# esp-module-ou.net
KiCad netlist of a schematic drawn in EAGLE
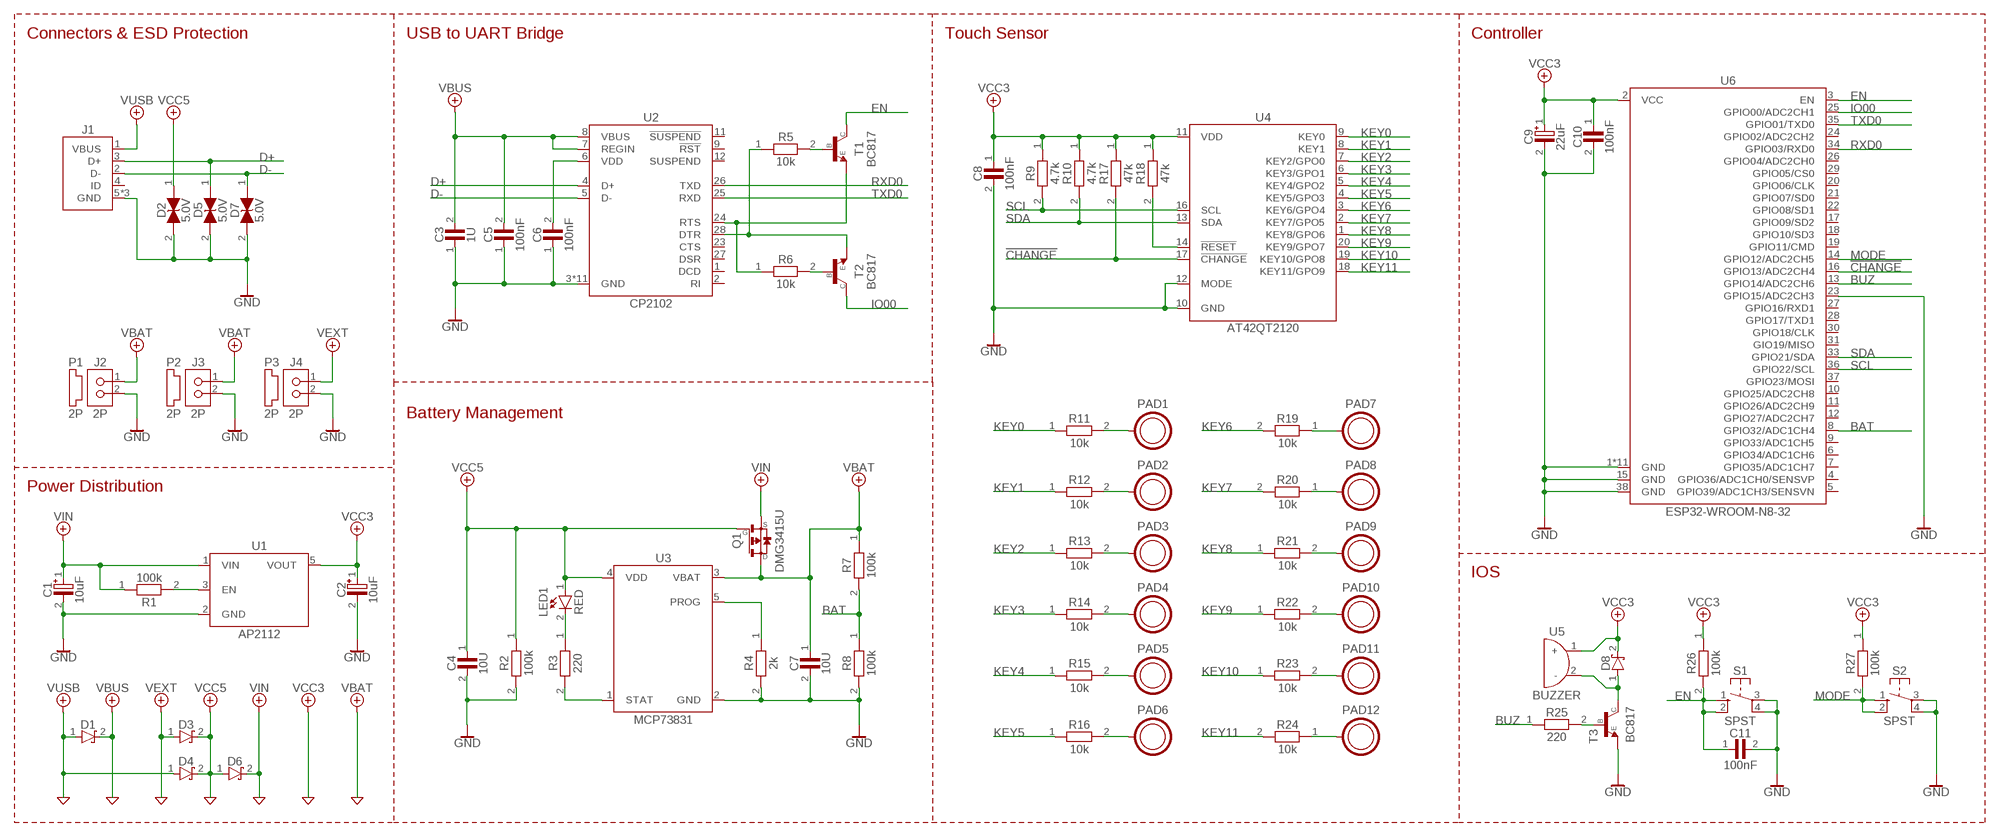
[diagram p0: schematic, sheet 1]

(export (version "E")
  (design (tool "Eeschema 10.0.6"))
  (components
    (comp (ref "C1")
      (value "10uF")
      (footprint "eagle-import:I1206-M3216-D")
      (fields
        (field (name "MF") "Kyocera AVX")
        (field (name "MPN") "TAJA106K016RNJ")
        (field (name "VOLTAGE") "16V")
      )
      (libsource (lib "eagle-import") (part "CAPACITOR-TANTALUM-I1206-M3216-10U"))
    )
    (comp (ref "C2")
      (value "10uF")
      (footprint "eagle-import:I1206-M3216-D")
      (fields
        (field (name "MF") "Kyocera AVX")
        (field (name "MPN") "TAJA106K016RNJ")
        (field (name "VOLTAGE") "16V")
      )
      (libsource (lib "eagle-import") (part "CAPACITOR-TANTALUM-I1206-M3216-10U"))
    )
    (comp (ref "C3")
      (value "1U")
      (footprint "eagle-import:I0805-M2012-C")
      (fields
        (field (name "MF") " FH (Guangdong Fenghua Advanced Tech)")
        (field (name "MPN") "0805B105K500NT")
        (field (name "TOLERANCE") "10%")
      )
      (libsource (lib "eagle-import") (part "CAPACITOR-CERAMIC-I0805-M2012-1U"))
    )
    (comp (ref "C4")
      (value "10U")
      (footprint "eagle-import:I0805-M2012-C")
      (fields
        (field (name "MF") "Samsung Electro-Mechanics")
        (field (name "MPN") "CL21A106KAYNNNE")
        (field (name "TOLERANCE") "10%")
      )
      (libsource (lib "eagle-import") (part "CAPACITOR-CERAMIC-I0805-M2012-10U"))
    )
    (comp (ref "C5")
      (value "100nF")
      (footprint "eagle-import:I0805-M2012-C")
      (fields
        (field (name "MF") "FH (Guangdong Fenghua Advanced Tech)")
        (field (name "MPN") "0805B104K500NT")
        (field (name "TOLERANCE") "10%")
      )
      (libsource (lib "eagle-import") (part "CAPACITOR-CERAMIC-I0805-M2012-100N"))
    )
    (comp (ref "C6")
      (value "100nF")
      (footprint "eagle-import:I0805-M2012-C")
      (fields
        (field (name "MF") "FH (Guangdong Fenghua Advanced Tech)")
        (field (name "MPN") "0805B104K500NT")
        (field (name "TOLERANCE") "10%")
      )
      (libsource (lib "eagle-import") (part "CAPACITOR-CERAMIC-I0805-M2012-100N"))
    )
    (comp (ref "C7")
      (value "10U")
      (footprint "eagle-import:I0805-M2012-C")
      (fields
        (field (name "MF") "Samsung Electro-Mechanics")
        (field (name "MPN") "CL21A106KAYNNNE")
        (field (name "TOLERANCE") "10%")
      )
      (libsource (lib "eagle-import") (part "CAPACITOR-CERAMIC-I0805-M2012-10U"))
    )
    (comp (ref "C8")
      (value "100nF")
      (footprint "eagle-import:I0805-M2012-C")
      (fields
        (field (name "MF") "FH (Guangdong Fenghua Advanced Tech)")
        (field (name "MPN") "0805B104K500NT")
        (field (name "TOLERANCE") "10%")
      )
      (libsource (lib "eagle-import") (part "CAPACITOR-CERAMIC-I0805-M2012-100N"))
    )
    (comp (ref "C9")
      (value "22uF")
      (footprint "eagle-import:I1206-M3216-D")
      (fields
        (field (name "MF") "Kyocera AVX")
        (field (name "MPN") "TAJA226K010RNJ")
        (field (name "VOLTAGE") "10V")
      )
      (libsource (lib "eagle-import") (part "CAPACITOR-TANTALUM-I1206-M3216-22U"))
    )
    (comp (ref "C10")
      (value "100nF")
      (footprint "eagle-import:I0805-M2012-C")
      (fields
        (field (name "MF") "FH (Guangdong Fenghua Advanced Tech)")
        (field (name "MPN") "0805B104K500NT")
        (field (name "TOLERANCE") "10%")
      )
      (libsource (lib "eagle-import") (part "CAPACITOR-CERAMIC-I0805-M2012-100N"))
    )
    (comp (ref "C11")
      (value "100nF")
      (footprint "eagle-import:I0805-M2012-C")
      (fields
        (field (name "MF") "FH (Guangdong Fenghua Advanced Tech)")
        (field (name "MPN") "0805B104K500NT")
        (field (name "TOLERANCE") "10%")
      )
      (libsource (lib "eagle-import") (part "CAPACITOR-CERAMIC-I0805-M2012-100N"))
    )
    (comp (ref "D1")
      (value "30V")
      (footprint "eagle-import:SOD-323")
      (fields (field (name "MF") "Diodes Incorporated") (field (name "MPN") "BAT760-7"))
      (libsource (lib "eagle-import") (part "SCHOTTKY-SOD-323-30V"))
    )
    (comp (ref "D2")
      (value "5.0V")
      (footprint "eagle-import:SOD-523")
      (fields (field (name "MF") " LRC") (field (name "MPN") "LESD5D5.0CT1G"))
      (libsource (lib "eagle-import") (part "ZENER-BI-SOD-523-5.0V"))
    )
    (comp (ref "D3")
      (value "30V")
      (footprint "eagle-import:SOD-323")
      (fields (field (name "MF") "Diodes Incorporated") (field (name "MPN") "BAT760-7"))
      (libsource (lib "eagle-import") (part "SCHOTTKY-SOD-323-30V"))
    )
    (comp (ref "D4")
      (value "30V")
      (footprint "eagle-import:SOD-323")
      (fields (field (name "MF") "Diodes Incorporated") (field (name "MPN") "BAT760-7"))
      (libsource (lib "eagle-import") (part "SCHOTTKY-SOD-323-30V"))
    )
    (comp (ref "D5")
      (value "5.0V")
      (footprint "eagle-import:SOD-523")
      (fields (field (name "MF") " LRC") (field (name "MPN") "LESD5D5.0CT1G"))
      (libsource (lib "eagle-import") (part "ZENER-BI-SOD-523-5.0V"))
    )
    (comp (ref "D6")
      (value "30V")
      (footprint "eagle-import:SOD-323")
      (fields (field (name "MF") "Diodes Incorporated") (field (name "MPN") "BAT760-7"))
      (libsource (lib "eagle-import") (part "SCHOTTKY-SOD-323-30V"))
    )
    (comp (ref "D7")
      (value "5.0V")
      (footprint "eagle-import:SOD-523")
      (fields (field (name "MF") " LRC") (field (name "MPN") "LESD5D5.0CT1G"))
      (libsource (lib "eagle-import") (part "ZENER-BI-SOD-523-5.0V"))
    )
    (comp (ref "D8")
      (value "30V")
      (footprint "eagle-import:SOD-323")
      (fields (field (name "MF") "Diodes Incorporated") (field (name "MPN") "BAT760-7"))
      (libsource (lib "eagle-import") (part "SCHOTTKY-SOD-323-30V"))
    )
    (comp (ref "J1")
      (value "USB-A-MICRO-TOP")
      (footprint "eagle-import:USB-A-MICRO-TOP")
      (fields (field (name "MF") "XKB Connectivity") (field (name "MPN") "U255-051N-4BH70-FS"))
      (libsource (lib "eagle-import") (part "USB-A-MICRO-TOP"))
    )
    (comp (ref "J2")
      (value "2P")
      (footprint "eagle-import:JST-S2B-PH-SM4-TB")
      (fields (field (name "MF") "JST Sales America") (field (name "MPN") "S2B-PH-SM4-TB(LF)(SN)"))
      (libsource (lib "eagle-import") (part "HEADER-02P-1R-S2B-PH-SM4-TB"))
    )
    (comp (ref "J3")
      (value "2P")
      (footprint "eagle-import:JST-S2B-PH-SM4-TB")
      (fields (field (name "MF") "JST Sales America") (field (name "MPN") "S2B-PH-SM4-TB(LF)(SN)"))
      (libsource (lib "eagle-import") (part "HEADER-02P-1R-S2B-PH-SM4-TB"))
    )
    (comp (ref "J4")
      (value "2P")
      (footprint "eagle-import:JST-S2B-PH-SM4-TB")
      (fields (field (name "MF") "JST Sales America") (field (name "MPN") "S2B-PH-SM4-TB(LF)(SN)"))
      (libsource (lib "eagle-import") (part "HEADER-02P-1R-S2B-PH-SM4-TB"))
    )
    (comp (ref "LED1")
      (value "RED")
      (footprint "eagle-import:I0805-M2012-D")
      (fields (field (name "MF") "Foshan NationStar Optoelectronics") (field (name "MPN") "FC-2012HRK-620D"))
      (libsource (lib "eagle-import") (part "LED-I0805-M2012-RED"))
    )
    (comp (ref "P1")
      (value "2P")
      (footprint "eagle-import:CONNECTOR-DEFAULT")
      (fields (field (name "MF") "JST Sales America") (field (name "MPN") "PHR-2"))
      (libsource (lib "eagle-import") (part "CONNECTOR-02P-1R-PHR"))
    )
    (comp (ref "P2")
      (value "2P")
      (footprint "eagle-import:CONNECTOR-DEFAULT")
      (fields (field (name "MF") "JST Sales America") (field (name "MPN") "PHR-2"))
      (libsource (lib "eagle-import") (part "CONNECTOR-02P-1R-PHR"))
    )
    (comp (ref "P3")
      (value "2P")
      (footprint "eagle-import:CONNECTOR-DEFAULT")
      (fields (field (name "MF") "JST Sales America") (field (name "MPN") "PHR-2"))
      (libsource (lib "eagle-import") (part "CONNECTOR-02P-1R-PHR"))
    )
    (comp (ref "PAD1")
      (value "QTOUCH")
      (footprint "eagle-import:QTOUCH")
      (libsource (lib "eagle-import") (part "QTOUCH"))
    )
    (comp (ref "PAD2")
      (value "QTOUCH")
      (footprint "eagle-import:QTOUCH")
      (libsource (lib "eagle-import") (part "QTOUCH"))
    )
    (comp (ref "PAD3")
      (value "QTOUCH")
      (footprint "eagle-import:QTOUCH")
      (libsource (lib "eagle-import") (part "QTOUCH"))
    )
    (comp (ref "PAD4")
      (value "QTOUCH")
      (footprint "eagle-import:QTOUCH")
      (libsource (lib "eagle-import") (part "QTOUCH"))
    )
    (comp (ref "PAD5")
      (value "QTOUCH")
      (footprint "eagle-import:QTOUCH")
      (libsource (lib "eagle-import") (part "QTOUCH"))
    )
    (comp (ref "PAD6")
      (value "QTOUCH")
      (footprint "eagle-import:QTOUCH")
      (libsource (lib "eagle-import") (part "QTOUCH"))
    )
    (comp (ref "PAD7")
      (value "QTOUCH")
      (footprint "eagle-import:QTOUCH")
      (libsource (lib "eagle-import") (part "QTOUCH"))
    )
    (comp (ref "PAD8")
      (value "QTOUCH")
      (footprint "eagle-import:QTOUCH")
      (libsource (lib "eagle-import") (part "QTOUCH"))
    )
    (comp (ref "PAD9")
      (value "QTOUCH")
      (footprint "eagle-import:QTOUCH")
      (libsource (lib "eagle-import") (part "QTOUCH"))
    )
    (comp (ref "PAD10")
      (value "QTOUCH")
      (footprint "eagle-import:QTOUCH")
      (libsource (lib "eagle-import") (part "QTOUCH"))
    )
    (comp (ref "PAD11")
      (value "QTOUCH")
      (footprint "eagle-import:QTOUCH")
      (libsource (lib "eagle-import") (part "QTOUCH"))
    )
    (comp (ref "PAD12")
      (value "QTOUCH")
      (footprint "eagle-import:QTOUCH")
      (libsource (lib "eagle-import") (part "QTOUCH"))
    )
    (comp (ref "Q1")
      (value "DMG3415U")
      (footprint "eagle-import:SOT-23-3")
      (fields
        (field (name "MF") "Diodes Incorporated")
        (field (name "MPN") "DMG3415U-7")
        (field (name "VOLTAGE") "20V")
      )
      (libsource (lib "eagle-import") (part "MOSFET-P-CHANNEL-SOT-23-3-20V-4A"))
    )
    (comp (ref "R1")
      (value "100k")
      (footprint "eagle-import:I0805-M2012-R")
      (fields (field (name "MF") "UNI-ROYAL(Uniroyal Elec)") (field (name "MPN") "0805W8F1003T5E"))
      (libsource (lib "eagle-import") (part "RESISTOR-I0805-M2012-100K"))
    )
    (comp (ref "R2")
      (value "100k")
      (footprint "eagle-import:I0805-M2012-R")
      (fields (field (name "MF") "UNI-ROYAL(Uniroyal Elec)") (field (name "MPN") "0805W8F1003T5E"))
      (libsource (lib "eagle-import") (part "RESISTOR-I0805-M2012-100K"))
    )
    (comp (ref "R3")
      (value "220")
      (footprint "eagle-import:I0805-M2012-R")
      (fields (field (name "MF") "UNI-ROYAL(Uniroyal Elec)") (field (name "MPN") "0805W8F2200T5E"))
      (libsource (lib "eagle-import") (part "RESISTOR-I0805-M2012-220"))
    )
    (comp (ref "R4")
      (value "2k")
      (footprint "eagle-import:I0805-M2012-R")
      (fields (field (name "MF") "UNI-ROYAL(Uniroyal Elec)") (field (name "MPN") "0805W8F2001T5E"))
      (libsource (lib "eagle-import") (part "RESISTOR-I0805-M2012-2K"))
    )
    (comp (ref "R5")
      (value "10k")
      (footprint "eagle-import:I0805-M2012-R")
      (fields (field (name "MF") " UNI-ROYAL(Uniroyal Elec)") (field (name "MPN") "0805W8F1002T5E"))
      (libsource (lib "eagle-import") (part "RESISTOR-I0805-M2012-10K"))
    )
    (comp (ref "R6")
      (value "10k")
      (footprint "eagle-import:I0805-M2012-R")
      (fields (field (name "MF") " UNI-ROYAL(Uniroyal Elec)") (field (name "MPN") "0805W8F1002T5E"))
      (libsource (lib "eagle-import") (part "RESISTOR-I0805-M2012-10K"))
    )
    (comp (ref "R7")
      (value "100k")
      (footprint "eagle-import:I0805-M2012-R")
      (fields (field (name "MF") "UNI-ROYAL(Uniroyal Elec)") (field (name "MPN") "0805W8F1003T5E"))
      (libsource (lib "eagle-import") (part "RESISTOR-I0805-M2012-100K"))
    )
    (comp (ref "R8")
      (value "100k")
      (footprint "eagle-import:I0805-M2012-R")
      (fields (field (name "MF") "UNI-ROYAL(Uniroyal Elec)") (field (name "MPN") "0805W8F1003T5E"))
      (libsource (lib "eagle-import") (part "RESISTOR-I0805-M2012-100K"))
    )
    (comp (ref "R9")
      (value "4.7k")
      (footprint "eagle-import:I0805-M2012-R")
      (fields (field (name "MF") " UNI-ROYAL(Uniroyal Elec)") (field (name "MPN") "0805W8F4701T5E"))
      (libsource (lib "eagle-import") (part "RESISTOR-I0805-M2012-4.7K"))
    )
    (comp (ref "R10")
      (value "4.7k")
      (footprint "eagle-import:I0805-M2012-R")
      (fields (field (name "MF") " UNI-ROYAL(Uniroyal Elec)") (field (name "MPN") "0805W8F4701T5E"))
      (libsource (lib "eagle-import") (part "RESISTOR-I0805-M2012-4.7K"))
    )
    (comp (ref "R11")
      (value "10k")
      (footprint "eagle-import:I0805-M2012-R")
      (fields (field (name "MF") " UNI-ROYAL(Uniroyal Elec)") (field (name "MPN") "0805W8F1002T5E"))
      (libsource (lib "eagle-import") (part "RESISTOR-I0805-M2012-10K"))
    )
    (comp (ref "R12")
      (value "10k")
      (footprint "eagle-import:I0805-M2012-R")
      (fields (field (name "MF") " UNI-ROYAL(Uniroyal Elec)") (field (name "MPN") "0805W8F1002T5E"))
      (libsource (lib "eagle-import") (part "RESISTOR-I0805-M2012-10K"))
    )
    (comp (ref "R13")
      (value "10k")
      (footprint "eagle-import:I0805-M2012-R")
      (fields (field (name "MF") " UNI-ROYAL(Uniroyal Elec)") (field (name "MPN") "0805W8F1002T5E"))
      (libsource (lib "eagle-import") (part "RESISTOR-I0805-M2012-10K"))
    )
    (comp (ref "R14")
      (value "10k")
      (footprint "eagle-import:I0805-M2012-R")
      (fields (field (name "MF") " UNI-ROYAL(Uniroyal Elec)") (field (name "MPN") "0805W8F1002T5E"))
      (libsource (lib "eagle-import") (part "RESISTOR-I0805-M2012-10K"))
    )
    (comp (ref "R15")
      (value "10k")
      (footprint "eagle-import:I0805-M2012-R")
      (fields (field (name "MF") " UNI-ROYAL(Uniroyal Elec)") (field (name "MPN") "0805W8F1002T5E"))
      (libsource (lib "eagle-import") (part "RESISTOR-I0805-M2012-10K"))
    )
    (comp (ref "R16")
      (value "10k")
      (footprint "eagle-import:I0805-M2012-R")
      (fields (field (name "MF") " UNI-ROYAL(Uniroyal Elec)") (field (name "MPN") "0805W8F1002T5E"))
      (libsource (lib "eagle-import") (part "RESISTOR-I0805-M2012-10K"))
    )
    (comp (ref "R17")
      (value "47k")
      (footprint "eagle-import:I0805-M2012-R")
      (fields (field (name "MF") "UNI-ROYAL(Uniroyal Elec)") (field (name "MPN") "0805W8F4702T5E"))
      (libsource (lib "eagle-import") (part "RESISTOR-I0805-M2012-47K"))
    )
    (comp (ref "R18")
      (value "47k")
      (footprint "eagle-import:I0805-M2012-R")
      (fields (field (name "MF") "UNI-ROYAL(Uniroyal Elec)") (field (name "MPN") "0805W8F4702T5E"))
      (libsource (lib "eagle-import") (part "RESISTOR-I0805-M2012-47K"))
    )
    (comp (ref "R19")
      (value "10k")
      (footprint "eagle-import:I0805-M2012-R")
      (fields (field (name "MF") " UNI-ROYAL(Uniroyal Elec)") (field (name "MPN") "0805W8F1002T5E"))
      (libsource (lib "eagle-import") (part "RESISTOR-I0805-M2012-10K"))
    )
    (comp (ref "R20")
      (value "10k")
      (footprint "eagle-import:I0805-M2012-R")
      (fields (field (name "MF") " UNI-ROYAL(Uniroyal Elec)") (field (name "MPN") "0805W8F1002T5E"))
      (libsource (lib "eagle-import") (part "RESISTOR-I0805-M2012-10K"))
    )
    (comp (ref "R21")
      (value "10k")
      (footprint "eagle-import:I0805-M2012-R")
      (fields (field (name "MF") " UNI-ROYAL(Uniroyal Elec)") (field (name "MPN") "0805W8F1002T5E"))
      (libsource (lib "eagle-import") (part "RESISTOR-I0805-M2012-10K"))
    )
    (comp (ref "R22")
      (value "10k")
      (footprint "eagle-import:I0805-M2012-R")
      (fields (field (name "MF") " UNI-ROYAL(Uniroyal Elec)") (field (name "MPN") "0805W8F1002T5E"))
      (libsource (lib "eagle-import") (part "RESISTOR-I0805-M2012-10K"))
    )
    (comp (ref "R23")
      (value "10k")
      (footprint "eagle-import:I0805-M2012-R")
      (fields (field (name "MF") " UNI-ROYAL(Uniroyal Elec)") (field (name "MPN") "0805W8F1002T5E"))
      (libsource (lib "eagle-import") (part "RESISTOR-I0805-M2012-10K"))
    )
    (comp (ref "R24")
      (value "10k")
      (footprint "eagle-import:I0805-M2012-R")
      (fields (field (name "MF") " UNI-ROYAL(Uniroyal Elec)") (field (name "MPN") "0805W8F1002T5E"))
      (libsource (lib "eagle-import") (part "RESISTOR-I0805-M2012-10K"))
    )
    (comp (ref "R25")
      (value "220")
      (footprint "eagle-import:I0805-M2012-R")
      (fields (field (name "MF") "UNI-ROYAL(Uniroyal Elec)") (field (name "MPN") "0805W8F2200T5E"))
      (libsource (lib "eagle-import") (part "RESISTOR-I0805-M2012-220"))
    )
    (comp (ref "R26")
      (value "100k")
      (footprint "eagle-import:I0805-M2012-R")
      (fields (field (name "MF") "UNI-ROYAL(Uniroyal Elec)") (field (name "MPN") "0805W8F1003T5E"))
      (libsource (lib "eagle-import") (part "RESISTOR-I0805-M2012-100K"))
    )
    (comp (ref "R27")
      (value "100k")
      (footprint "eagle-import:I0805-M2012-R")
      (fields (field (name "MF") "UNI-ROYAL(Uniroyal Elec)") (field (name "MPN") "0805W8F1003T5E"))
      (libsource (lib "eagle-import") (part "RESISTOR-I0805-M2012-100K"))
    )
    (comp (ref "S1")
      (value "SPST")
      (footprint "eagle-import:SMD-SW-4")
      (fields
        (field (name "MF") "XKB Enterprise")
        (field (name "MPN") "TS-1187A-B-A-B")
        (field (name "VOLTAGE") "12V")
      )
      (libsource (lib "eagle-import") (part "SWITCH-12V-50MA"))
    )
    (comp (ref "S2")
      (value "SPST")
      (footprint "eagle-import:SMD-SW-4")
      (fields
        (field (name "MF") "XKB Enterprise")
        (field (name "MPN") "TS-1187A-B-A-B")
        (field (name "VOLTAGE") "12V")
      )
      (libsource (lib "eagle-import") (part "SWITCH-12V-50MA"))
    )
    (comp (ref "T1")
      (value "BC817")
      (footprint "eagle-import:SOT-23-3")
      (fields (field (name "MF") " Nexperia") (field (name "MPN") " BC817-40,215"))
      (libsource (lib "eagle-import") (part "TRANSISTOR-NPN-SOT-23-3"))
    )
    (comp (ref "T2")
      (value "BC817")
      (footprint "eagle-import:SOT-23-3")
      (fields (field (name "MF") " Nexperia") (field (name "MPN") " BC817-40,215"))
      (libsource (lib "eagle-import") (part "TRANSISTOR-NPN-SOT-23-3"))
    )
    (comp (ref "T3")
      (value "BC817")
      (footprint "eagle-import:SOT-23-3")
      (fields (field (name "MF") " Nexperia") (field (name "MPN") " BC817-40,215"))
      (libsource (lib "eagle-import") (part "TRANSISTOR-NPN-SOT-23-3"))
    )
    (comp (ref "U1")
      (value "AP2112")
      (footprint "eagle-import:SOT-25-5")
      (fields (field (name "MF") "TECH PUBLIC") (field (name "MPN") "TPAP2112K-3.3TRG1"))
      (libsource (lib "eagle-import") (part "AP2112-SOT-25-5"))
    )
    (comp (ref "U2")
      (value "CP2102")
      (footprint "eagle-import:QFN-28")
      (fields (field (name "MF") "SILICON LABS") (field (name "MPN") "CP2102-GMR"))
      (libsource (lib "eagle-import") (part "CP2102-QFN-28"))
    )
    (comp (ref "U3")
      (value "MCP73831")
      (footprint "eagle-import:SOT-23-5")
      (fields (field (name "MF") "Microchip Tech") (field (name "MPN") "MCP73831T-2ATI/OT"))
      (libsource (lib "eagle-import") (part "MCP73831-SOT-23-5"))
    )
    (comp (ref "U4")
      (value "AT42QT2120")
      (footprint "eagle-import:TSSOP-20")
      (fields (field (name "MF") "Microchip Tech") (field (name "MPN") "AT42QT2120-XU"))
      (libsource (lib "eagle-import") (part "AT42QT2120-TSSOP-20"))
    )
    (comp (ref "U5")
      (value "BUZZER")
      (footprint "eagle-import:SMD-BUZZER")
      (fields (field (name "MF") "MLT-7525") (field (name "MPN") "Jiangsu Huaneng Elec"))
      (libsource (lib "eagle-import") (part "BUZZER"))
    )
    (comp (ref "U6")
      (value "ESP32-WROOM-N8-32")
      (footprint "eagle-import:ESP32-WROOM-32")
      (fields (field (name "MF") "Espressif Systems") (field (name "MPN") " ESP32-WROOM-32-N8"))
      (libsource (lib "eagle-import") (part "ESP32-WROOM-32-N8"))
    )
  )
  (nets
    (net (code "1") (name "/BAT") (class "Default")
      (node (ref "R7") (pin "2") (pinfunction "2_2") (pintype "passive"))
      (node (ref "R8") (pin "1") (pinfunction "1_1") (pintype "passive"))
      (node (ref "U6") (pin "8") (pinfunction "GPIO32/ADC1CH4_8") (pintype "bidirectional"))
    )
    (net (code "2") (name "/BUZ") (class "Default")
      (node (ref "R25") (pin "1") (pinfunction "1_1") (pintype "passive"))
      (node (ref "U6") (pin "13") (pinfunction "GPIO14/ADC2CH6_13") (pintype "bidirectional"))
    )
    (net (code "3") (name "/D+") (class "Default")
      (node (ref "D5") (pin "1") (pinfunction "A_1") (pintype "passive"))
      (node (ref "J1") (pin "3") (pinfunction "D+_3") (pintype "bidirectional"))
      (node (ref "U2") (pin "4") (pinfunction "D+_4") (pintype "bidirectional"))
    )
    (net (code "4") (name "/D-") (class "Default")
      (node (ref "D7") (pin "1") (pinfunction "A_1") (pintype "passive"))
      (node (ref "J1") (pin "2") (pinfunction "D-_2") (pintype "bidirectional"))
      (node (ref "U2") (pin "5") (pinfunction "D-_5") (pintype "bidirectional"))
    )
    (net (code "5") (name "/EN") (class "Default")
      (node (ref "C11") (pin "1") (pinfunction "1_1") (pintype "passive"))
      (node (ref "R26") (pin "2") (pinfunction "2_2") (pintype "passive"))
      (node (ref "S1") (pin "1") (pinfunction "1_1") (pintype "bidirectional"))
      (node (ref "S1") (pin "2") (pinfunction "2_2") (pintype "bidirectional"))
      (node (ref "T1") (pin "3") (pinfunction "C_3") (pintype "passive"))
      (node (ref "U6") (pin "3") (pinfunction "EN_3") (pintype "bidirectional"))
    )
    (net (code "6") (name "/IO00") (class "Default")
      (node (ref "T2") (pin "3") (pinfunction "C_3") (pintype "passive"))
      (node (ref "U6") (pin "25") (pinfunction "GPIO00/ADC2CH1_25") (pintype "bidirectional"))
    )
    (net (code "7") (name "/KEY0") (class "Default")
      (node (ref "R11") (pin "1") (pinfunction "1_1") (pintype "passive"))
      (node (ref "U4") (pin "9") (pinfunction "KEY0_9") (pintype "bidirectional"))
    )
    (net (code "8") (name "/KEY1") (class "Default")
      (node (ref "R12") (pin "1") (pinfunction "1_1") (pintype "passive"))
      (node (ref "U4") (pin "8") (pinfunction "KEY1_8") (pintype "bidirectional"))
    )
    (net (code "9") (name "/KEY2") (class "Default")
      (node (ref "R13") (pin "1") (pinfunction "1_1") (pintype "passive"))
      (node (ref "U4") (pin "7") (pinfunction "KEY2/GPO0_7") (pintype "bidirectional"))
    )
    (net (code "10") (name "/KEY3") (class "Default")
      (node (ref "R14") (pin "1") (pinfunction "1_1") (pintype "passive"))
      (node (ref "U4") (pin "6") (pinfunction "KEY3/GPO1_6") (pintype "bidirectional"))
    )
    (net (code "11") (name "/KEY4") (class "Default")
      (node (ref "R15") (pin "1") (pinfunction "1_1") (pintype "passive"))
      (node (ref "U4") (pin "5") (pinfunction "KEY4/GPO2_5") (pintype "bidirectional"))
    )
    (net (code "12") (name "/KEY5") (class "Default")
      (node (ref "R16") (pin "1") (pinfunction "1_1") (pintype "passive"))
      (node (ref "U4") (pin "4") (pinfunction "KEY5/GPO3_4") (pintype "bidirectional"))
    )
    (net (code "13") (name "/KEY6") (class "Default")
      (node (ref "R19") (pin "2") (pinfunction "2_2") (pintype "passive"))
      (node (ref "U4") (pin "3") (pinfunction "KEY6/GPO4_3") (pintype "bidirectional"))
    )
    (net (code "14") (name "/KEY7") (class "Default")
      (node (ref "R20") (pin "2") (pinfunction "2_2") (pintype "passive"))
      (node (ref "U4") (pin "2") (pinfunction "KEY7/GPO5_2") (pintype "bidirectional"))
    )
    (net (code "15") (name "/KEY8") (class "Default")
      (node (ref "R21") (pin "1") (pinfunction "1_1") (pintype "passive"))
      (node (ref "U4") (pin "1") (pinfunction "KEY8/GPO6_1") (pintype "bidirectional"))
    )
    (net (code "16") (name "/KEY9") (class "Default")
      (node (ref "R22") (pin "1") (pinfunction "1_1") (pintype "passive"))
      (node (ref "U4") (pin "20") (pinfunction "KEY9/GPO7_20") (pintype "bidirectional"))
    )
    (net (code "17") (name "/KEY10") (class "Default")
      (node (ref "R23") (pin "1") (pinfunction "1_1") (pintype "passive"))
      (node (ref "U4") (pin "19") (pinfunction "KEY10/GPO8_19") (pintype "bidirectional"))
    )
    (net (code "18") (name "/KEY11") (class "Default")
      (node (ref "R24") (pin "2") (pinfunction "2_2") (pintype "passive"))
      (node (ref "U4") (pin "18") (pinfunction "KEY11/GPO9_18") (pintype "bidirectional"))
    )
    (net (code "19") (name "/MODE") (class "Default")
      (node (ref "R27") (pin "2") (pinfunction "2_2") (pintype "passive"))
      (node (ref "S2") (pin "1") (pinfunction "1_1") (pintype "bidirectional"))
      (node (ref "S2") (pin "2") (pinfunction "2_2") (pintype "bidirectional"))
      (node (ref "U6") (pin "14") (pinfunction "GPIO12/ADC2CH5_14") (pintype "bidirectional"))
    )
    (net (code "20") (name "/RXD0") (class "Default")
      (node (ref "U2") (pin "26") (pinfunction "TXD_26") (pintype "bidirectional"))
      (node (ref "U6") (pin "34") (pinfunction "GPIO03/RXD0_34") (pintype "bidirectional"))
    )
    (net (code "21") (name "/SCL") (class "Default")
      (node (ref "R9") (pin "2") (pinfunction "2_2") (pintype "passive"))
      (node (ref "U4") (pin "16") (pinfunction "SCL_16") (pintype "bidirectional"))
      (node (ref "U6") (pin "36") (pinfunction "GPIO22/SCL_36") (pintype "bidirectional"))
    )
    (net (code "22") (name "/SDA") (class "Default")
      (node (ref "R10") (pin "2") (pinfunction "2_2") (pintype "passive"))
      (node (ref "U4") (pin "13") (pinfunction "SDA_13") (pintype "bidirectional"))
      (node (ref "U6") (pin "33") (pinfunction "GPIO21/SDA_33") (pintype "bidirectional"))
    )
    (net (code "23") (name "/TXD0") (class "Default")
      (node (ref "U2") (pin "25") (pinfunction "RXD_25") (pintype "bidirectional"))
      (node (ref "U6") (pin "35") (pinfunction "GPIO01/TXD0_35") (pintype "bidirectional"))
    )
    (net (code "24") (name "/~{CHANGE}") (class "Default")
      (node (ref "R17") (pin "2") (pinfunction "2_2") (pintype "passive"))
      (node (ref "U4") (pin "17") (pinfunction "~{CHANGE}_17") (pintype "output"))
      (node (ref "U6") (pin "16") (pinfunction "GPIO13/ADC2CH4_16") (pintype "bidirectional"))
    )
    (net (code "25") (name "GND") (class "Default")
      (node (ref "C1") (pin "2") (pinfunction "-_2") (pintype "passive"))
      (node (ref "C10") (pin "2") (pinfunction "2_2") (pintype "passive"))
      (node (ref "C11") (pin "2") (pinfunction "2_2") (pintype "passive"))
      (node (ref "C2") (pin "2") (pinfunction "-_2") (pintype "passive"))
      (node (ref "C3") (pin "1") (pinfunction "1_1") (pintype "passive"))
      (node (ref "C4") (pin "2") (pinfunction "2_2") (pintype "passive"))
      (node (ref "C5") (pin "1") (pinfunction "1_1") (pintype "passive"))
      (node (ref "C6") (pin "1") (pinfunction "1_1") (pintype "passive"))
      (node (ref "C7") (pin "2") (pinfunction "2_2") (pintype "passive"))
      (node (ref "C8") (pin "2") (pinfunction "2_2") (pintype "passive"))
      (node (ref "C9") (pin "2") (pinfunction "-_2") (pintype "passive"))
      (node (ref "D2") (pin "2") (pinfunction "C_2") (pintype "passive"))
      (node (ref "D5") (pin "2") (pinfunction "C_2") (pintype "passive"))
      (node (ref "D7") (pin "2") (pinfunction "C_2") (pintype "passive"))
      (node (ref "J1") (pin "5") (pinfunction "GND_5") (pintype "power_in"))
      (node (ref "J1") (pin "6") (pinfunction "GND_6") (pintype "power_in"))
      (node (ref "J1") (pin "7") (pinfunction "GND_7") (pintype "power_in"))
      (node (ref "J2") (pin "2") (pinfunction "02_2") (pintype "passive"))
      (node (ref "J3") (pin "2") (pinfunction "02_2") (pintype "passive"))
      (node (ref "J4") (pin "2") (pinfunction "02_2") (pintype "passive"))
      (node (ref "R2") (pin "2") (pinfunction "2_2") (pintype "passive"))
      (node (ref "R4") (pin "2") (pinfunction "2_2") (pintype "passive"))
      (node (ref "R8") (pin "2") (pinfunction "2_2") (pintype "passive"))
      (node (ref "S1") (pin "3") (pinfunction "3_3") (pintype "bidirectional"))
      (node (ref "S1") (pin "4") (pinfunction "4_4") (pintype "bidirectional"))
      (node (ref "S2") (pin "3") (pinfunction "3_3") (pintype "bidirectional"))
      (node (ref "S2") (pin "4") (pinfunction "4_4") (pintype "bidirectional"))
      (node (ref "T3") (pin "2") (pinfunction "E_2") (pintype "passive"))
      (node (ref "U1") (pin "2") (pinfunction "GND_2") (pintype "power_in"))
      (node (ref "U2") (pin "29") (pinfunction "GND_29") (pintype "power_in"))
      (node (ref "U2") (pin "3") (pinfunction "GND_3") (pintype "power_in"))
      (node (ref "U2") (pin "30") (pinfunction "GND_30") (pintype "power_in"))
      (node (ref "U2") (pin "31") (pinfunction "GND_31") (pintype "power_in"))
      (node (ref "U2") (pin "32") (pinfunction "GND_32") (pintype "power_in"))
      (node (ref "U2") (pin "33") (pinfunction "GND_33") (pintype "power_in"))
      (node (ref "U2") (pin "34") (pinfunction "GND_34") (pintype "power_in"))
      (node (ref "U2") (pin "35") (pinfunction "GND_35") (pintype "power_in"))
      (node (ref "U2") (pin "36") (pinfunction "GND_36") (pintype "power_in"))
      (node (ref "U2") (pin "37") (pinfunction "GND_37") (pintype "power_in"))
      (node (ref "U2") (pin "38") (pinfunction "GND_38") (pintype "power_in"))
      (node (ref "U3") (pin "2") (pinfunction "GND_2") (pintype "power_in"))
      (node (ref "U4") (pin "10") (pinfunction "GND_10") (pintype "power_in"))
      (node (ref "U4") (pin "12") (pinfunction "MODE_12") (pintype "bidirectional"))
      (node (ref "U6") (pin "1") (pinfunction "GND_1") (pintype "power_in"))
      (node (ref "U6") (pin "15") (pinfunction "GND_15") (pintype "power_in"))
      (node (ref "U6") (pin "23") (pinfunction "GPIO15/ADC2CH3_23") (pintype "bidirectional"))
      (node (ref "U6") (pin "38") (pinfunction "GND_38") (pintype "bidirectional"))
      (node (ref "U6") (pin "39") (pinfunction "GND_39") (pintype "power_in"))
      (node (ref "U6") (pin "40") (pinfunction "GND_40") (pintype "power_in"))
      (node (ref "U6") (pin "41") (pinfunction "GND_41") (pintype "power_in"))
      (node (ref "U6") (pin "42") (pinfunction "GND_42") (pintype "power_in"))
      (node (ref "U6") (pin "43") (pinfunction "GND_43") (pintype "power_in"))
      (node (ref "U6") (pin "44") (pinfunction "GND_44") (pintype "power_in"))
      (node (ref "U6") (pin "45") (pinfunction "GND_45") (pintype "power_in"))
      (node (ref "U6") (pin "46") (pinfunction "GND_46") (pintype "power_in"))
      (node (ref "U6") (pin "47") (pinfunction "GND_47") (pintype "power_in"))
      (node (ref "U6") (pin "48") (pinfunction "GND_48") (pintype "power_in"))
    )
    (net (code "26") (name "Net-(D8-A)") (class "Default")
      (node (ref "D8") (pin "1") (pinfunction "A_1") (pintype "passive"))
      (node (ref "T3") (pin "3") (pinfunction "C_3") (pintype "passive"))
      (node (ref "U5") (pin "2") (pinfunction "-_2") (pintype "bidirectional"))
    )
    (net (code "27") (name "Net-(LED1-C)") (class "Default")
      (node (ref "LED1") (pin "2") (pinfunction "C_2") (pintype "passive"))
      (node (ref "R3") (pin "1") (pinfunction "1_1") (pintype "passive"))
    )
    (net (code "28") (name "Net-(PAD1-PAD)") (class "Default")
      (node (ref "PAD1") (pin "1") (pinfunction "PAD_1") (pintype "passive"))
      (node (ref "R11") (pin "2") (pinfunction "2_2") (pintype "passive"))
    )
    (net (code "29") (name "Net-(PAD2-PAD)") (class "Default")
      (node (ref "PAD2") (pin "1") (pinfunction "PAD_1") (pintype "passive"))
      (node (ref "R12") (pin "2") (pinfunction "2_2") (pintype "passive"))
    )
    (net (code "30") (name "Net-(PAD3-PAD)") (class "Default")
      (node (ref "PAD3") (pin "1") (pinfunction "PAD_1") (pintype "passive"))
      (node (ref "R13") (pin "2") (pinfunction "2_2") (pintype "passive"))
    )
    (net (code "31") (name "Net-(PAD4-PAD)") (class "Default")
      (node (ref "PAD4") (pin "1") (pinfunction "PAD_1") (pintype "passive"))
      (node (ref "R14") (pin "2") (pinfunction "2_2") (pintype "passive"))
    )
    (net (code "32") (name "Net-(PAD5-PAD)") (class "Default")
      (node (ref "PAD5") (pin "1") (pinfunction "PAD_1") (pintype "passive"))
      (node (ref "R15") (pin "2") (pinfunction "2_2") (pintype "passive"))
    )
    (net (code "33") (name "Net-(PAD6-PAD)") (class "Default")
      (node (ref "PAD6") (pin "1") (pinfunction "PAD_1") (pintype "passive"))
      (node (ref "R16") (pin "2") (pinfunction "2_2") (pintype "passive"))
    )
    (net (code "34") (name "Net-(PAD7-PAD)") (class "Default")
      (node (ref "PAD7") (pin "1") (pinfunction "PAD_1") (pintype "passive"))
      (node (ref "R19") (pin "1") (pinfunction "1_1") (pintype "passive"))
    )
    (net (code "35") (name "Net-(PAD8-PAD)") (class "Default")
      (node (ref "PAD8") (pin "1") (pinfunction "PAD_1") (pintype "passive"))
      (node (ref "R20") (pin "1") (pinfunction "1_1") (pintype "passive"))
    )
    (net (code "36") (name "Net-(PAD9-PAD)") (class "Default")
      (node (ref "PAD9") (pin "1") (pinfunction "PAD_1") (pintype "passive"))
      (node (ref "R21") (pin "2") (pinfunction "2_2") (pintype "passive"))
    )
    (net (code "37") (name "Net-(PAD10-PAD)") (class "Default")
      (node (ref "PAD10") (pin "1") (pinfunction "PAD_1") (pintype "passive"))
      (node (ref "R22") (pin "2") (pinfunction "2_2") (pintype "passive"))
    )
    (net (code "38") (name "Net-(PAD11-PAD)") (class "Default")
      (node (ref "PAD11") (pin "1") (pinfunction "PAD_1") (pintype "passive"))
      (node (ref "R23") (pin "2") (pinfunction "2_2") (pintype "passive"))
    )
    (net (code "39") (name "Net-(PAD12-PAD)") (class "Default")
      (node (ref "PAD12") (pin "1") (pinfunction "PAD_1") (pintype "passive"))
      (node (ref "R24") (pin "1") (pinfunction "1_1") (pintype "passive"))
    )
    (net (code "40") (name "Net-(T1-B)") (class "Default")
      (node (ref "R5") (pin "2") (pinfunction "2_2") (pintype "passive"))
      (node (ref "T1") (pin "1") (pinfunction "B_1") (pintype "passive"))
    )
    (net (code "41") (name "Net-(T1-E)") (class "Default")
      (node (ref "R6") (pin "1") (pinfunction "1_1") (pintype "passive"))
      (node (ref "T1") (pin "2") (pinfunction "E_2") (pintype "passive"))
      (node (ref "U2") (pin "24") (pinfunction "RTS_24") (pintype "bidirectional"))
    )
    (net (code "42") (name "Net-(T2-B)") (class "Default")
      (node (ref "R6") (pin "2") (pinfunction "2_2") (pintype "passive"))
      (node (ref "T2") (pin "1") (pinfunction "B_1") (pintype "passive"))
    )
    (net (code "43") (name "Net-(T2-E)") (class "Default")
      (node (ref "R5") (pin "1") (pinfunction "1_1") (pintype "passive"))
      (node (ref "T2") (pin "2") (pinfunction "E_2") (pintype "passive"))
      (node (ref "U2") (pin "28") (pinfunction "DTR_28") (pintype "bidirectional"))
    )
    (net (code "44") (name "Net-(T3-B)") (class "Default")
      (node (ref "R25") (pin "2") (pinfunction "2_2") (pintype "passive"))
      (node (ref "T3") (pin "1") (pinfunction "B_1") (pintype "passive"))
    )
    (net (code "45") (name "Net-(U1-EN)") (class "Default")
      (node (ref "R1") (pin "2") (pinfunction "2_2") (pintype "passive"))
      (node (ref "U1") (pin "3") (pinfunction "EN_3") (pintype "bidirectional"))
    )
    (net (code "46") (name "Net-(U2-VDD)") (class "Default")
      (node (ref "C6") (pin "2") (pinfunction "2_2") (pintype "passive"))
      (node (ref "U2") (pin "6") (pinfunction "VDD_6") (pintype "power_in"))
    )
    (net (code "47") (name "Net-(U3-PROG)") (class "Default")
      (node (ref "R4") (pin "1") (pinfunction "1_1") (pintype "passive"))
      (node (ref "U3") (pin "5") (pinfunction "PROG_5") (pintype "bidirectional"))
    )
    (net (code "48") (name "Net-(U3-STAT)") (class "Default")
      (node (ref "R3") (pin "2") (pinfunction "2_2") (pintype "passive"))
      (node (ref "U3") (pin "1") (pinfunction "STAT_1") (pintype "bidirectional"))
    )
    (net (code "49") (name "Net-(U4-~{RESET})") (class "Default")
      (node (ref "R18") (pin "2") (pinfunction "2_2") (pintype "passive"))
      (node (ref "U4") (pin "14") (pinfunction "~{RESET}_14") (pintype "bidirectional"))
    )
    (net (code "50") (name "VBAT") (class "Default")
      (node (ref "C7") (pin "1") (pinfunction "1_1") (pintype "passive"))
      (node (ref "J2") (pin "1") (pinfunction "01_1") (pintype "passive"))
      (node (ref "J3") (pin "1") (pinfunction "01_1") (pintype "passive"))
      (node (ref "Q1") (pin "3") (pinfunction "D_3") (pintype "passive"))
      (node (ref "R7") (pin "1") (pinfunction "1_1") (pintype "passive"))
      (node (ref "U3") (pin "3") (pinfunction "VBAT_3") (pintype "bidirectional"))
    )
    (net (code "51") (name "VBUS") (class "Default")
      (node (ref "C3") (pin "2") (pinfunction "2_2") (pintype "passive"))
      (node (ref "C5") (pin "2") (pinfunction "2_2") (pintype "passive"))
      (node (ref "D1") (pin "2") (pinfunction "C_2") (pintype "passive"))
      (node (ref "U2") (pin "7") (pinfunction "REGIN_7") (pintype "bidirectional"))
      (node (ref "U2") (pin "8") (pinfunction "VBUS_8") (pintype "bidirectional"))
    )
    (net (code "52") (name "VCC3") (class "Default")
      (node (ref "C10") (pin "1") (pinfunction "1_1") (pintype "passive"))
      (node (ref "C2") (pin "1") (pinfunction "+_1") (pintype "passive"))
      (node (ref "C8") (pin "1") (pinfunction "1_1") (pintype "passive"))
      (node (ref "C9") (pin "1") (pinfunction "+_1") (pintype "passive"))
      (node (ref "D8") (pin "2") (pinfunction "C_2") (pintype "passive"))
      (node (ref "R10") (pin "1") (pinfunction "1_1") (pintype "passive"))
      (node (ref "R17") (pin "1") (pinfunction "1_1") (pintype "passive"))
      (node (ref "R18") (pin "1") (pinfunction "1_1") (pintype "passive"))
      (node (ref "R26") (pin "1") (pinfunction "1_1") (pintype "passive"))
      (node (ref "R27") (pin "1") (pinfunction "1_1") (pintype "passive"))
      (node (ref "R9") (pin "1") (pinfunction "1_1") (pintype "passive"))
      (node (ref "U1") (pin "5") (pinfunction "VOUT_5") (pintype "power_in"))
      (node (ref "U4") (pin "11") (pinfunction "VDD_11") (pintype "power_in"))
      (node (ref "U5") (pin "1") (pinfunction "+_1") (pintype "bidirectional"))
      (node (ref "U6") (pin "2") (pinfunction "VCC_2") (pintype "power_in"))
    )
    (net (code "53") (name "VCC5") (class "Default")
      (node (ref "C4") (pin "1") (pinfunction "1_1") (pintype "passive"))
      (node (ref "D2") (pin "1") (pinfunction "A_1") (pintype "passive"))
      (node (ref "D3") (pin "2") (pinfunction "C_2") (pintype "passive"))
      (node (ref "D4") (pin "2") (pinfunction "C_2") (pintype "passive"))
      (node (ref "D6") (pin "1") (pinfunction "A_1") (pintype "passive"))
      (node (ref "LED1") (pin "1") (pinfunction "A_1") (pintype "passive"))
      (node (ref "Q1") (pin "1") (pinfunction "G_1") (pintype "passive"))
      (node (ref "R2") (pin "1") (pinfunction "1_1") (pintype "passive"))
      (node (ref "U3") (pin "4") (pinfunction "VDD_4") (pintype "power_in"))
    )
    (net (code "54") (name "VEXT") (class "Default")
      (node (ref "D3") (pin "1") (pinfunction "A_1") (pintype "passive"))
      (node (ref "J4") (pin "1") (pinfunction "01_1") (pintype "passive"))
    )
    (net (code "55") (name "VIN") (class "Default")
      (node (ref "C1") (pin "1") (pinfunction "+_1") (pintype "passive"))
      (node (ref "D6") (pin "2") (pinfunction "C_2") (pintype "passive"))
      (node (ref "Q1") (pin "2") (pinfunction "S_2") (pintype "passive"))
      (node (ref "R1") (pin "1") (pinfunction "1_1") (pintype "passive"))
      (node (ref "U1") (pin "1") (pinfunction "VIN_1") (pintype "power_in"))
    )
    (net (code "56") (name "VUSB") (class "Default")
      (node (ref "D1") (pin "1") (pinfunction "A_1") (pintype "passive"))
      (node (ref "D4") (pin "1") (pinfunction "A_1") (pintype "passive"))
      (node (ref "J1") (pin "1") (pinfunction "VBUS_1") (pintype "power_in"))
    )
    (net (code "57") (name "unconnected-(J1-ID-Pad4)") (class "Default")
      (node (ref "J1") (pin "4") (pinfunction "ID_4") (pintype "passive"))
    )
    (net (code "58") (name "unconnected-(U2-CTS-Pad23)") (class "Default")
      (node (ref "U2") (pin "23") (pinfunction "CTS_23") (pintype "bidirectional"))
    )
    (net (code "59") (name "unconnected-(U2-DCD-Pad1)") (class "Default")
      (node (ref "U2") (pin "1") (pinfunction "DCD_1") (pintype "bidirectional"))
    )
    (net (code "60") (name "unconnected-(U2-DSR-Pad27)") (class "Default")
      (node (ref "U2") (pin "27") (pinfunction "DSR_27") (pintype "bidirectional"))
    )
    (net (code "61") (name "unconnected-(U2-RI-Pad2)") (class "Default")
      (node (ref "U2") (pin "2") (pinfunction "RI_2") (pintype "bidirectional"))
    )
    (net (code "62") (name "unconnected-(U2-SUSPEND-Pad12)") (class "Default")
      (node (ref "U2") (pin "12") (pinfunction "SUSPEND_12") (pintype "bidirectional"))
    )
    (net (code "63") (name "unconnected-(U2-~{RST}-Pad9)") (class "Default")
      (node (ref "U2") (pin "9") (pinfunction "~{RST}_9") (pintype "bidirectional"))
    )
    (net (code "64") (name "unconnected-(U2-~{SUSPEND}-Pad11)") (class "Default")
      (node (ref "U2") (pin "11") (pinfunction "~{SUSPEND}_11") (pintype "bidirectional"))
    )
    (net (code "65") (name "unconnected-(U6-GIO19{slash}MISO-Pad31)") (class "Default")
      (node (ref "U6") (pin "31") (pinfunction "GIO19/MISO_31") (pintype "bidirectional"))
    )
    (net (code "66") (name "unconnected-(U6-GPIO02{slash}ADC2CH2-Pad24)") (class "Default")
      (node (ref "U6") (pin "24") (pinfunction "GPIO02/ADC2CH2_24") (pintype "bidirectional"))
    )
    (net (code "67") (name "unconnected-(U6-GPIO04{slash}ADC2CH0-Pad26)") (class "Default")
      (node (ref "U6") (pin "26") (pinfunction "GPIO04/ADC2CH0_26") (pintype "bidirectional"))
    )
    (net (code "68") (name "unconnected-(U6-GPIO05{slash}CS0-Pad29)") (class "Default")
      (node (ref "U6") (pin "29") (pinfunction "GPIO05/CS0_29") (pintype "bidirectional"))
    )
    (net (code "69") (name "unconnected-(U6-GPIO06{slash}CLK-Pad20)") (class "Default")
      (node (ref "U6") (pin "20") (pinfunction "GPIO06/CLK_20") (pintype "bidirectional"))
    )
    (net (code "70") (name "unconnected-(U6-GPIO07{slash}SD0-Pad21)") (class "Default")
      (node (ref "U6") (pin "21") (pinfunction "GPIO07/SD0_21") (pintype "bidirectional"))
    )
    (net (code "71") (name "unconnected-(U6-GPIO08{slash}SD1-Pad22)") (class "Default")
      (node (ref "U6") (pin "22") (pinfunction "GPIO08/SD1_22") (pintype "bidirectional"))
    )
    (net (code "72") (name "unconnected-(U6-GPIO09{slash}SD2-Pad17)") (class "Default")
      (node (ref "U6") (pin "17") (pinfunction "GPIO09/SD2_17") (pintype "bidirectional"))
    )
    (net (code "73") (name "unconnected-(U6-GPIO10{slash}SD3-Pad18)") (class "Default")
      (node (ref "U6") (pin "18") (pinfunction "GPIO10/SD3_18") (pintype "bidirectional"))
    )
    (net (code "74") (name "unconnected-(U6-GPIO11{slash}CMD-Pad19)") (class "Default")
      (node (ref "U6") (pin "19") (pinfunction "GPIO11/CMD_19") (pintype "bidirectional"))
    )
    (net (code "75") (name "unconnected-(U6-GPIO16{slash}RXD1-Pad27)") (class "Default")
      (node (ref "U6") (pin "27") (pinfunction "GPIO16/RXD1_27") (pintype "bidirectional"))
    )
    (net (code "76") (name "unconnected-(U6-GPIO17{slash}TXD1-Pad28)") (class "Default")
      (node (ref "U6") (pin "28") (pinfunction "GPIO17/TXD1_28") (pintype "bidirectional"))
    )
    (net (code "77") (name "unconnected-(U6-GPIO18{slash}CLK-Pad30)") (class "Default")
      (node (ref "U6") (pin "30") (pinfunction "GPIO18/CLK_30") (pintype "bidirectional"))
    )
    (net (code "78") (name "unconnected-(U6-GPIO23{slash}MOSI-Pad37)") (class "Default")
      (node (ref "U6") (pin "37") (pinfunction "GPIO23/MOSI_37") (pintype "bidirectional"))
    )
    (net (code "79") (name "unconnected-(U6-GPIO25{slash}ADC2CH8-Pad10)") (class "Default")
      (node (ref "U6") (pin "10") (pinfunction "GPIO25/ADC2CH8_10") (pintype "bidirectional"))
    )
    (net (code "80") (name "unconnected-(U6-GPIO26{slash}ADC2CH9-Pad11)") (class "Default")
      (node (ref "U6") (pin "11") (pinfunction "GPIO26/ADC2CH9_11") (pintype "bidirectional"))
    )
    (net (code "81") (name "unconnected-(U6-GPIO27{slash}ADC2CH7-Pad12)") (class "Default")
      (node (ref "U6") (pin "12") (pinfunction "GPIO27/ADC2CH7_12") (pintype "bidirectional"))
    )
    (net (code "82") (name "unconnected-(U6-GPIO33{slash}ADC1CH5-Pad9)") (class "Default")
      (node (ref "U6") (pin "9") (pinfunction "GPIO33/ADC1CH5_9") (pintype "bidirectional"))
    )
    (net (code "83") (name "unconnected-(U6-GPIO34{slash}ADC1CH6-Pad6)") (class "Default")
      (node (ref "U6") (pin "6") (pinfunction "GPIO34/ADC1CH6_6") (pintype "bidirectional"))
    )
    (net (code "84") (name "unconnected-(U6-GPIO35{slash}ADC1CH7-Pad7)") (class "Default")
      (node (ref "U6") (pin "7") (pinfunction "GPIO35/ADC1CH7_7") (pintype "bidirectional"))
    )
    (net (code "85") (name "unconnected-(U6-GPIO36{slash}ADC1CH0{slash}SENSVP-Pad4)") (class "Default")
      (node (ref "U6") (pin "4") (pinfunction "GPIO36/ADC1CH0/SENSVP_4") (pintype "bidirectional"))
    )
    (net (code "86") (name "unconnected-(U6-GPIO39{slash}ADC1CH3{slash}SENSVN-Pad5)") (class "Default")
      (node (ref "U6") (pin "5") (pinfunction "GPIO39/ADC1CH3/SENSVN_5") (pintype "bidirectional"))
    )
  )
)
